# Power1.net
KiCad netlist of a schematic drawn in Altium Designer
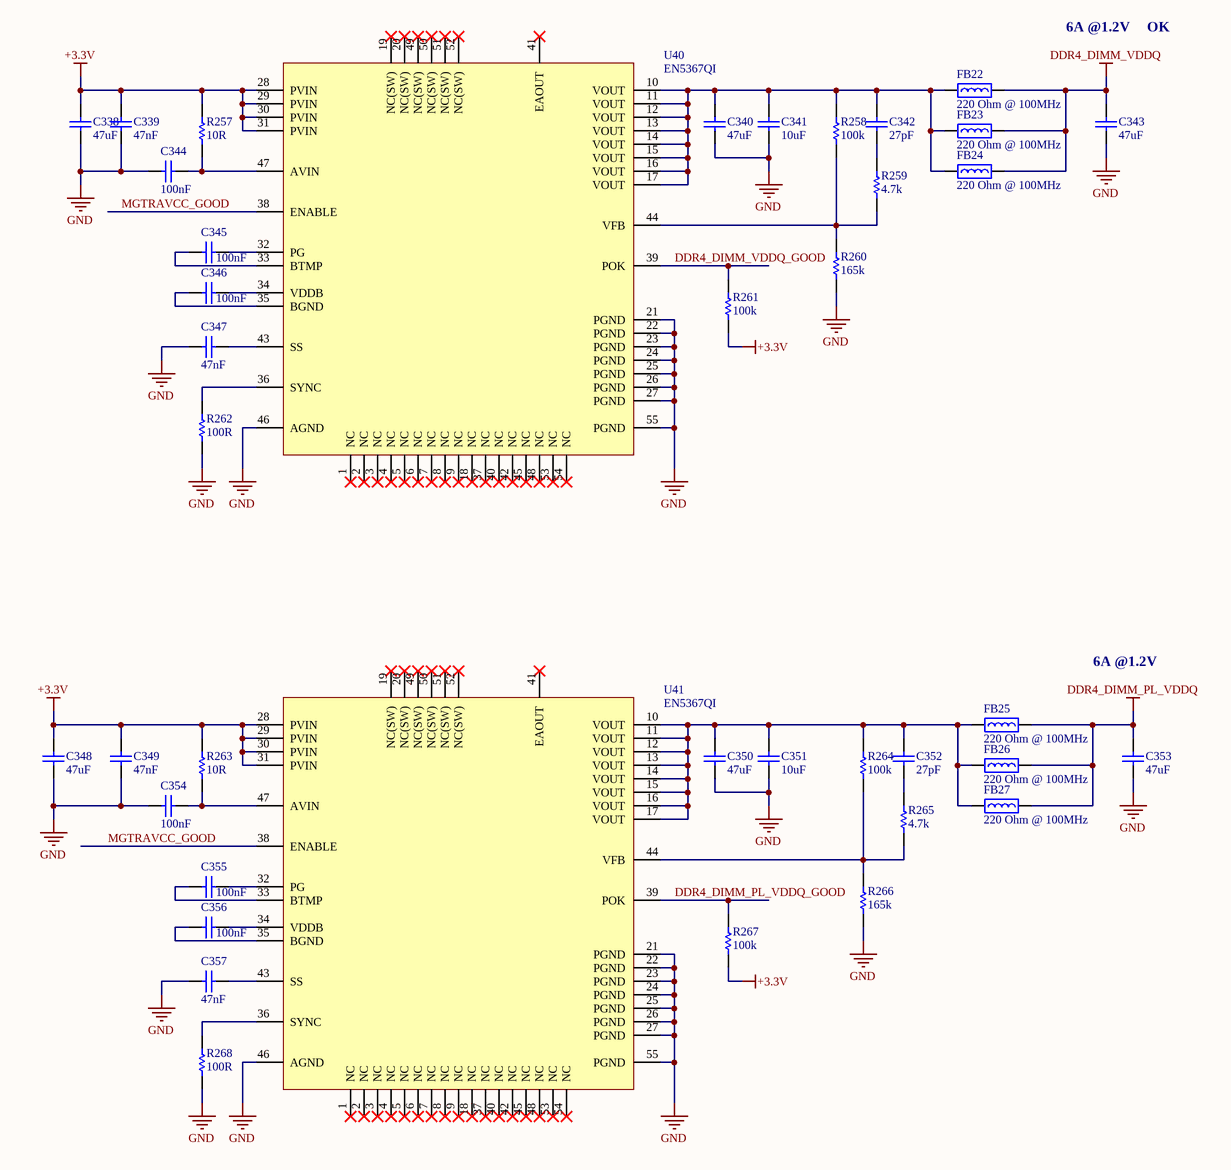
[diagram p0: Power1.SchDoc]

(export (version "E")
  (design (tool "Eeschema 10.0.6"))
  (components
    (comp (ref "C338")
      (value "47uF")
      (footprint "CAPC3216L_1206")
      (description "CAP CER 47UF 25V X5R 1206")
      (fields (field (name "VOLTAGE") "25V") (field (name "TOLERANCE") "20%"))
      (libsource (lib "Ultrascale_SchLib") (part "CAPCER1206X5R47U25V_20T"))
    )
    (comp (ref "C339")
      (value "47nF")
      (footprint "CAPC2012L_0805")
      (description "CAP CER 0.047UF 50V X7R 0805")
      (fields (field (name "VOLTAGE") "50V") (field (name "TOLERANCE") "10%"))
      (libsource (lib "Ultrascale_SchLib") (part "CAPCER0805X5R47N50V_10T"))
    )
    (comp (ref "C340")
      (value "47uF")
      (footprint "CAPC3216L_1206")
      (description "CAP CER 47UF 25V X5R 1206")
      (fields (field (name "VOLTAGE") "25V") (field (name "TOLERANCE") "20%"))
      (libsource (lib "Ultrascale_SchLib") (part "CAPCER1206X5R47U25V_20T"))
    )
    (comp (ref "C341")
      (value "10uF")
      (footprint "CAPC1005L_0402")
      (description "CAP CER 10UF 10V X5R 0402")
      (fields (field (name "VOLTAGE") "10V") (field (name "TOLERANCE") "20%"))
      (libsource (lib "Ultrascale_SchLib") (part "CAPCER0402X5R10U10V_20T"))
    )
    (comp (ref "C342")
      (value "27pF")
      (footprint "CAPC1005L_0402")
      (description "CAP CER 27PF 50V C0G/NP0 0402")
      (fields (field (name "VOLTAGE") "50V") (field (name "TOLERANCE") "5%"))
      (libsource (lib "Ultrascale_SchLib") (part "CAPCER0402C0G27P50V_5T"))
    )
    (comp (ref "C343")
      (value "47uF")
      (footprint "CAPC3216L_1206")
      (description "CAP CER 47UF 25V X5R 1206")
      (fields (field (name "VOLTAGE") "25V") (field (name "TOLERANCE") "20%"))
      (libsource (lib "Ultrascale_SchLib") (part "CAPCER1206X5R47U25V_20T"))
    )
    (comp (ref "C344")
      (value "100nF")
      (footprint "CAPC1005L_0402")
      (description "CAP CER 0.1UF 25V X7R 0402")
      (fields (field (name "VOLTAGE") "25V") (field (name "TOLERANCE") "10%"))
      (libsource (lib "Ultrascale_SchLib") (part "CAPCER0402X7R100N25V_10T"))
    )
    (comp (ref "C345")
      (value "100nF")
      (footprint "CAPC1005L_0402")
      (description "CAP CER 0.1UF 25V X7R 0402")
      (fields (field (name "VOLTAGE") "25V") (field (name "TOLERANCE") "10%"))
      (libsource (lib "Ultrascale_SchLib") (part "CAPCER0402X7R100N25V_10T"))
    )
    (comp (ref "C346")
      (value "100nF")
      (footprint "CAPC1005L_0402")
      (description "CAP CER 0.1UF 25V X7R 0402")
      (fields (field (name "VOLTAGE") "25V") (field (name "TOLERANCE") "10%"))
      (libsource (lib "Ultrascale_SchLib") (part "CAPCER0402X7R100N25V_10T"))
    )
    (comp (ref "C347")
      (value "47nF")
      (footprint "CAPC2012L_0805")
      (description "CAP CER 0.047UF 50V X7R 0805")
      (fields (field (name "VOLTAGE") "50V") (field (name "TOLERANCE") "10%"))
      (libsource (lib "Ultrascale_SchLib") (part "CAPCER0805X5R47N50V_10T"))
    )
    (comp (ref "C348")
      (value "47uF")
      (footprint "CAPC3216L_1206")
      (description "CAP CER 47UF 25V X5R 1206")
      (fields (field (name "VOLTAGE") "25V") (field (name "TOLERANCE") "20%"))
      (libsource (lib "Ultrascale_SchLib") (part "CAPCER1206X5R47U25V_20T"))
    )
    (comp (ref "C349")
      (value "47nF")
      (footprint "CAPC2012L_0805")
      (description "CAP CER 0.047UF 50V X7R 0805")
      (fields (field (name "VOLTAGE") "50V") (field (name "TOLERANCE") "10%"))
      (libsource (lib "Ultrascale_SchLib") (part "CAPCER0805X5R47N50V_10T"))
    )
    (comp (ref "C350")
      (value "47uF")
      (footprint "CAPC3216L_1206")
      (description "CAP CER 47UF 25V X5R 1206")
      (fields (field (name "VOLTAGE") "25V") (field (name "TOLERANCE") "20%"))
      (libsource (lib "Ultrascale_SchLib") (part "CAPCER1206X5R47U25V_20T"))
    )
    (comp (ref "C351")
      (value "10uF")
      (footprint "CAPC1005L_0402")
      (description "CAP CER 10UF 10V X5R 0402")
      (fields (field (name "VOLTAGE") "10V") (field (name "TOLERANCE") "20%"))
      (libsource (lib "Ultrascale_SchLib") (part "CAPCER0402X5R10U10V_20T"))
    )
    (comp (ref "C352")
      (value "27pF")
      (footprint "CAPC1005L_0402")
      (description "CAP CER 27PF 50V C0G/NP0 0402")
      (fields (field (name "VOLTAGE") "50V") (field (name "TOLERANCE") "5%"))
      (libsource (lib "Ultrascale_SchLib") (part "CAPCER0402C0G27P50V_5T"))
    )
    (comp (ref "C353")
      (value "47uF")
      (footprint "CAPC3216L_1206")
      (description "CAP CER 47UF 25V X5R 1206")
      (fields (field (name "VOLTAGE") "25V") (field (name "TOLERANCE") "20%"))
      (libsource (lib "Ultrascale_SchLib") (part "CAPCER1206X5R47U25V_20T"))
    )
    (comp (ref "C354")
      (value "100nF")
      (footprint "CAPC1005L_0402")
      (description "CAP CER 0.1UF 25V X7R 0402")
      (fields (field (name "VOLTAGE") "25V") (field (name "TOLERANCE") "10%"))
      (libsource (lib "Ultrascale_SchLib") (part "CAPCER0402X7R100N25V_10T"))
    )
    (comp (ref "C355")
      (value "100nF")
      (footprint "CAPC1005L_0402")
      (description "CAP CER 0.1UF 25V X7R 0402")
      (fields (field (name "VOLTAGE") "25V") (field (name "TOLERANCE") "10%"))
      (libsource (lib "Ultrascale_SchLib") (part "CAPCER0402X7R100N25V_10T"))
    )
    (comp (ref "C356")
      (value "100nF")
      (footprint "CAPC1005L_0402")
      (description "CAP CER 0.1UF 25V X7R 0402")
      (fields (field (name "VOLTAGE") "25V") (field (name "TOLERANCE") "10%"))
      (libsource (lib "Ultrascale_SchLib") (part "CAPCER0402X7R100N25V_10T"))
    )
    (comp (ref "C357")
      (value "47nF")
      (footprint "CAPC2012L_0805")
      (description "CAP CER 0.047UF 50V X7R 0805")
      (fields (field (name "VOLTAGE") "50V") (field (name "TOLERANCE") "10%"))
      (libsource (lib "Ultrascale_SchLib") (part "CAPCER0805X5R47N50V_10T"))
    )
    (comp (ref "FB22")
      (value "BEAD0603_220_2A5_40M")
      (footprint "INDC1608N_0603")
      (description "FERRITE BEAD 220 OHM 0603 1LN")
      (fields (field (name "IMPEDANCE @ FREQUENCY") "220 Ohm @ 100MHz"))
      (libsource (lib "Ultrascale_SchLib") (part "BEAD0603_220_2A5_40M"))
    )
    (comp (ref "FB23")
      (value "BEAD0603_220_2A5_40M")
      (footprint "INDC1608N_0603")
      (description "FERRITE BEAD 220 OHM 0603 1LN")
      (fields (field (name "IMPEDANCE @ FREQUENCY") "220 Ohm @ 100MHz"))
      (libsource (lib "Ultrascale_SchLib") (part "BEAD0603_220_2A5_40M"))
    )
    (comp (ref "FB24")
      (value "BEAD0603_220_2A5_40M")
      (footprint "INDC1608N_0603")
      (description "FERRITE BEAD 220 OHM 0603 1LN")
      (fields (field (name "IMPEDANCE @ FREQUENCY") "220 Ohm @ 100MHz"))
      (libsource (lib "Ultrascale_SchLib") (part "BEAD0603_220_2A5_40M"))
    )
    (comp (ref "FB25")
      (value "BEAD0603_220_2A5_40M")
      (footprint "INDC1608N_0603")
      (description "FERRITE BEAD 220 OHM 0603 1LN")
      (fields (field (name "IMPEDANCE @ FREQUENCY") "220 Ohm @ 100MHz"))
      (libsource (lib "Ultrascale_SchLib") (part "BEAD0603_220_2A5_40M"))
    )
    (comp (ref "FB26")
      (value "BEAD0603_220_2A5_40M")
      (footprint "INDC1608N_0603")
      (description "FERRITE BEAD 220 OHM 0603 1LN")
      (fields (field (name "IMPEDANCE @ FREQUENCY") "220 Ohm @ 100MHz"))
      (libsource (lib "Ultrascale_SchLib") (part "BEAD0603_220_2A5_40M"))
    )
    (comp (ref "FB27")
      (value "BEAD0603_220_2A5_40M")
      (footprint "INDC1608N_0603")
      (description "FERRITE BEAD 220 OHM 0603 1LN")
      (fields (field (name "IMPEDANCE @ FREQUENCY") "220 Ohm @ 100MHz"))
      (libsource (lib "Ultrascale_SchLib") (part "BEAD0603_220_2A5_40M"))
    )
    (comp (ref "R257")
      (value "10R")
      (footprint "RESC1005L_0402")
      (description "RES SMD 10 OHM 1% 1/10W 0402")
      (fields (field (name "POWER") "1/10W") (field (name "TOLERANCE") "1%"))
      (libsource (lib "Ultrascale_SchLib") (part "RES0402_10R_0W1_1T"))
    )
    (comp (ref "R258")
      (value "100k")
      (footprint "RESC1005L_0402")
      (description "RES SMD 100K OHM 1% 1/5W 0402")
      (fields (field (name "POWER") "1/5W") (field (name "TOLERANCE") "1%"))
      (libsource (lib "Ultrascale_SchLib") (part "RES0402_100K_0W2_1T"))
    )
    (comp (ref "R259")
      (value "4.7k")
      (footprint "RESC1005L_0402")
      (description "RES SMD 4.7K OHM 1% 1/10W 0402")
      (fields (field (name "POWER") "1/10W") (field (name "TOLERANCE") "1%"))
      (libsource (lib "Ultrascale_SchLib") (part "RES0402_4K7_0W1_1T"))
    )
    (comp (ref "R260")
      (value "165k")
      (footprint "RESC1005L_0402")
      (description "RES SMD 165K OHM 1% 1/10W 0402")
      (fields (field (name "POWER") "1/10W") (field (name "TOLERANCE") "±1%"))
      (libsource (lib "Ultrascale_SchLib") (part "RES0402_165K_0W1_1T"))
    )
    (comp (ref "R261")
      (value "100k")
      (footprint "RESC1005L_0402")
      (description "RES SMD 100K OHM 1% 1/5W 0402")
      (fields (field (name "POWER") "1/5W") (field (name "TOLERANCE") "1%"))
      (libsource (lib "Ultrascale_SchLib") (part "RES0402_100K_0W2_1T"))
    )
    (comp (ref "R262")
      (value "100R")
      (footprint "RESC1005L_0402")
      (description "RES SMD 100 OHM 1% 1/10W 0402")
      (fields (field (name "POWER") "1/10W") (field (name "TOLERANCE") "1%"))
      (libsource (lib "Ultrascale_SchLib") (part "RES0402_100R_0W1_1T"))
    )
    (comp (ref "R263")
      (value "10R")
      (footprint "RESC1005L_0402")
      (description "RES SMD 10 OHM 1% 1/10W 0402")
      (fields (field (name "POWER") "1/10W") (field (name "TOLERANCE") "1%"))
      (libsource (lib "Ultrascale_SchLib") (part "RES0402_10R_0W1_1T"))
    )
    (comp (ref "R264")
      (value "100k")
      (footprint "RESC1005L_0402")
      (description "RES SMD 100K OHM 1% 1/5W 0402")
      (fields (field (name "POWER") "1/5W") (field (name "TOLERANCE") "1%"))
      (libsource (lib "Ultrascale_SchLib") (part "RES0402_100K_0W2_1T"))
    )
    (comp (ref "R265")
      (value "4.7k")
      (footprint "RESC1005L_0402")
      (description "RES SMD 4.7K OHM 1% 1/10W 0402")
      (fields (field (name "POWER") "1/10W") (field (name "TOLERANCE") "1%"))
      (libsource (lib "Ultrascale_SchLib") (part "RES0402_4K7_0W1_1T"))
    )
    (comp (ref "R266")
      (value "165k")
      (footprint "RESC1005L_0402")
      (description "RES SMD 165K OHM 1% 1/10W 0402")
      (fields (field (name "POWER") "1/10W") (field (name "TOLERANCE") "±1%"))
      (libsource (lib "Ultrascale_SchLib") (part "RES0402_165K_0W1_1T"))
    )
    (comp (ref "R267")
      (value "100k")
      (footprint "RESC1005L_0402")
      (description "RES SMD 100K OHM 1% 1/5W 0402")
      (fields (field (name "POWER") "1/5W") (field (name "TOLERANCE") "1%"))
      (libsource (lib "Ultrascale_SchLib") (part "RES0402_100K_0W2_1T"))
    )
    (comp (ref "R268")
      (value "100R")
      (footprint "RESC1005L_0402")
      (description "RES SMD 100 OHM 1% 1/10W 0402")
      (fields (field (name "POWER") "1/10W") (field (name "TOLERANCE") "1%"))
      (libsource (lib "Ultrascale_SchLib") (part "RES0402_100R_0W1_1T"))
    )
    (comp (ref "U40")
      (value "EN5367QI")
      (footprint "QFN54-EN5367QI")
      (description "DC/DC CONVERTER 0.6-4.9V 29W")
      (libsource (lib "Ultrascale_SchLib") (part "EN5367QI"))
    )
    (comp (ref "U41")
      (value "EN5367QI")
      (footprint "QFN54-EN5367QI")
      (description "DC/DC CONVERTER 0.6-4.9V 29W")
      (libsource (lib "Ultrascale_SchLib") (part "EN5367QI"))
    )
  )
  (nets
    (net (code "1") (name "+3.3V") (class "Default")
      (node (ref "C338") (pin "2") (pinfunction "2_2") (pintype "passive"))
      (node (ref "C339") (pin "2") (pinfunction "2_2") (pintype "passive"))
      (node (ref "C348") (pin "2") (pinfunction "2_2") (pintype "passive"))
      (node (ref "C349") (pin "2") (pinfunction "2_2") (pintype "passive"))
      (node (ref "R257") (pin "2") (pinfunction "2_2") (pintype "passive"))
      (node (ref "R261") (pin "2") (pinfunction "2_2") (pintype "passive"))
      (node (ref "R263") (pin "2") (pinfunction "2_2") (pintype "passive"))
      (node (ref "R267") (pin "2") (pinfunction "2_2") (pintype "passive"))
      (node (ref "U40") (pin "28") (pinfunction "PVIN_28") (pintype "power_in"))
      (node (ref "U40") (pin "29") (pinfunction "PVIN_29") (pintype "power_in"))
      (node (ref "U40") (pin "30") (pinfunction "PVIN_30") (pintype "power_in"))
      (node (ref "U40") (pin "31") (pinfunction "PVIN_31") (pintype "power_in"))
      (node (ref "U41") (pin "28") (pinfunction "PVIN_28") (pintype "power_in"))
      (node (ref "U41") (pin "29") (pinfunction "PVIN_29") (pintype "power_in"))
      (node (ref "U41") (pin "30") (pinfunction "PVIN_30") (pintype "power_in"))
      (node (ref "U41") (pin "31") (pinfunction "PVIN_31") (pintype "power_in"))
    )
    (net (code "2") (name "/DDR4_DIMM_PL_VDDQ_GOOD") (class "Default")
      (node (ref "R267") (pin "1") (pinfunction "1_1") (pintype "passive"))
      (node (ref "U41") (pin "39") (pinfunction "POK_39") (pintype "power_in"))
    )
    (net (code "3") (name "/DDR4_DIMM_VDDQ_GOOD") (class "Default")
      (node (ref "R261") (pin "1") (pinfunction "1_1") (pintype "passive"))
      (node (ref "U40") (pin "39") (pinfunction "POK_39") (pintype "power_in"))
    )
    (net (code "4") (name "/MGTRAVCC_GOOD") (class "Default")
      (node (ref "U40") (pin "38") (pinfunction "ENABLE_38") (pintype "power_in"))
      (node (ref "U41") (pin "38") (pinfunction "ENABLE_38") (pintype "power_in"))
    )
    (net (code "5") (name "DDR4_DIMM_PL_VDDQ") (class "Default")
      (node (ref "C353") (pin "2") (pinfunction "2_2") (pintype "passive"))
      (node (ref "FB25") (pin "2") (pinfunction "2_2") (pintype "passive"))
      (node (ref "FB26") (pin "2") (pinfunction "2_2") (pintype "passive"))
      (node (ref "FB27") (pin "2") (pinfunction "2_2") (pintype "passive"))
    )
    (net (code "6") (name "DDR4_DIMM_VDDQ") (class "Default")
      (node (ref "C343") (pin "2") (pinfunction "2_2") (pintype "passive"))
      (node (ref "FB22") (pin "2") (pinfunction "2_2") (pintype "passive"))
      (node (ref "FB23") (pin "2") (pinfunction "2_2") (pintype "passive"))
      (node (ref "FB24") (pin "2") (pinfunction "2_2") (pintype "passive"))
    )
    (net (code "7") (name "GND") (class "Default")
      (node (ref "C338") (pin "1") (pinfunction "1_1") (pintype "passive"))
      (node (ref "C339") (pin "1") (pinfunction "1_1") (pintype "passive"))
      (node (ref "C340") (pin "1") (pinfunction "1_1") (pintype "passive"))
      (node (ref "C341") (pin "1") (pinfunction "1_1") (pintype "passive"))
      (node (ref "C343") (pin "1") (pinfunction "1_1") (pintype "passive"))
      (node (ref "C344") (pin "2") (pinfunction "2_2") (pintype "passive"))
      (node (ref "C347") (pin "2") (pinfunction "2_2") (pintype "passive"))
      (node (ref "C348") (pin "1") (pinfunction "1_1") (pintype "passive"))
      (node (ref "C349") (pin "1") (pinfunction "1_1") (pintype "passive"))
      (node (ref "C350") (pin "1") (pinfunction "1_1") (pintype "passive"))
      (node (ref "C351") (pin "1") (pinfunction "1_1") (pintype "passive"))
      (node (ref "C353") (pin "1") (pinfunction "1_1") (pintype "passive"))
      (node (ref "C354") (pin "2") (pinfunction "2_2") (pintype "passive"))
      (node (ref "C357") (pin "2") (pinfunction "2_2") (pintype "passive"))
      (node (ref "R260") (pin "1") (pinfunction "1_1") (pintype "passive"))
      (node (ref "R262") (pin "2") (pinfunction "2_2") (pintype "passive"))
      (node (ref "R266") (pin "1") (pinfunction "1_1") (pintype "passive"))
      (node (ref "R268") (pin "2") (pinfunction "2_2") (pintype "passive"))
      (node (ref "U40") (pin "21") (pinfunction "PGND_21") (pintype "power_in"))
      (node (ref "U40") (pin "22") (pinfunction "PGND_22") (pintype "power_in"))
      (node (ref "U40") (pin "23") (pinfunction "PGND_23") (pintype "power_in"))
      (node (ref "U40") (pin "24") (pinfunction "PGND_24") (pintype "power_in"))
      (node (ref "U40") (pin "25") (pinfunction "PGND_25") (pintype "power_in"))
      (node (ref "U40") (pin "26") (pinfunction "PGND_26") (pintype "power_in"))
      (node (ref "U40") (pin "27") (pinfunction "PGND_27") (pintype "power_in"))
      (node (ref "U40") (pin "46") (pinfunction "AGND_46") (pintype "power_in"))
      (node (ref "U40") (pin "55") (pinfunction "PGND_55") (pintype "power_in"))
      (node (ref "U41") (pin "21") (pinfunction "PGND_21") (pintype "power_in"))
      (node (ref "U41") (pin "22") (pinfunction "PGND_22") (pintype "power_in"))
      (node (ref "U41") (pin "23") (pinfunction "PGND_23") (pintype "power_in"))
      (node (ref "U41") (pin "24") (pinfunction "PGND_24") (pintype "power_in"))
      (node (ref "U41") (pin "25") (pinfunction "PGND_25") (pintype "power_in"))
      (node (ref "U41") (pin "26") (pinfunction "PGND_26") (pintype "power_in"))
      (node (ref "U41") (pin "27") (pinfunction "PGND_27") (pintype "power_in"))
      (node (ref "U41") (pin "46") (pinfunction "AGND_46") (pintype "power_in"))
      (node (ref "U41") (pin "55") (pinfunction "PGND_55") (pintype "power_in"))
    )
    (net (code "8") (name "Net-(C340-Pad2)") (class "Default")
      (node (ref "C340") (pin "2") (pinfunction "2_2") (pintype "passive"))
      (node (ref "C341") (pin "2") (pinfunction "2_2") (pintype "passive"))
      (node (ref "C342") (pin "2") (pinfunction "2_2") (pintype "passive"))
      (node (ref "FB22") (pin "1") (pinfunction "1_1") (pintype "passive"))
      (node (ref "FB23") (pin "1") (pinfunction "1_1") (pintype "passive"))
      (node (ref "FB24") (pin "1") (pinfunction "1_1") (pintype "passive"))
      (node (ref "R258") (pin "2") (pinfunction "2_2") (pintype "passive"))
      (node (ref "U40") (pin "10") (pinfunction "VOUT_10") (pintype "power_in"))
      (node (ref "U40") (pin "11") (pinfunction "VOUT_11") (pintype "power_in"))
      (node (ref "U40") (pin "12") (pinfunction "VOUT_12") (pintype "power_in"))
      (node (ref "U40") (pin "13") (pinfunction "VOUT_13") (pintype "power_in"))
      (node (ref "U40") (pin "14") (pinfunction "VOUT_14") (pintype "power_in"))
      (node (ref "U40") (pin "15") (pinfunction "VOUT_15") (pintype "power_in"))
      (node (ref "U40") (pin "16") (pinfunction "VOUT_16") (pintype "power_in"))
      (node (ref "U40") (pin "17") (pinfunction "VOUT_17") (pintype "power_in"))
    )
    (net (code "9") (name "Net-(C342-Pad1)") (class "Default")
      (node (ref "C342") (pin "1") (pinfunction "1_1") (pintype "passive"))
      (node (ref "R259") (pin "2") (pinfunction "2_2") (pintype "passive"))
    )
    (net (code "10") (name "Net-(C350-Pad2)") (class "Default")
      (node (ref "C350") (pin "2") (pinfunction "2_2") (pintype "passive"))
      (node (ref "C351") (pin "2") (pinfunction "2_2") (pintype "passive"))
      (node (ref "C352") (pin "2") (pinfunction "2_2") (pintype "passive"))
      (node (ref "FB25") (pin "1") (pinfunction "1_1") (pintype "passive"))
      (node (ref "FB26") (pin "1") (pinfunction "1_1") (pintype "passive"))
      (node (ref "FB27") (pin "1") (pinfunction "1_1") (pintype "passive"))
      (node (ref "R264") (pin "2") (pinfunction "2_2") (pintype "passive"))
      (node (ref "U41") (pin "10") (pinfunction "VOUT_10") (pintype "power_in"))
      (node (ref "U41") (pin "11") (pinfunction "VOUT_11") (pintype "power_in"))
      (node (ref "U41") (pin "12") (pinfunction "VOUT_12") (pintype "power_in"))
      (node (ref "U41") (pin "13") (pinfunction "VOUT_13") (pintype "power_in"))
      (node (ref "U41") (pin "14") (pinfunction "VOUT_14") (pintype "power_in"))
      (node (ref "U41") (pin "15") (pinfunction "VOUT_15") (pintype "power_in"))
      (node (ref "U41") (pin "16") (pinfunction "VOUT_16") (pintype "power_in"))
      (node (ref "U41") (pin "17") (pinfunction "VOUT_17") (pintype "power_in"))
    )
    (net (code "11") (name "Net-(C352-Pad1)") (class "Default")
      (node (ref "C352") (pin "1") (pinfunction "1_1") (pintype "passive"))
      (node (ref "R265") (pin "2") (pinfunction "2_2") (pintype "passive"))
    )
    (net (code "12") (name "Net-(U40-AVIN)") (class "Default")
      (node (ref "C344") (pin "1") (pinfunction "1_1") (pintype "passive"))
      (node (ref "R257") (pin "1") (pinfunction "1_1") (pintype "passive"))
      (node (ref "U40") (pin "47") (pinfunction "AVIN_47") (pintype "power_in"))
    )
    (net (code "13") (name "Net-(U40-BGND)") (class "Default")
      (node (ref "C346") (pin "2") (pinfunction "2_2") (pintype "passive"))
      (node (ref "U40") (pin "35") (pinfunction "BGND_35") (pintype "power_in"))
    )
    (net (code "14") (name "Net-(U40-BTMP)") (class "Default")
      (node (ref "C345") (pin "2") (pinfunction "2_2") (pintype "passive"))
      (node (ref "U40") (pin "33") (pinfunction "BTMP_33") (pintype "power_in"))
    )
    (net (code "15") (name "Net-(U40-PG)") (class "Default")
      (node (ref "C345") (pin "1") (pinfunction "1_1") (pintype "passive"))
      (node (ref "U40") (pin "32") (pinfunction "PG_32") (pintype "power_in"))
    )
    (net (code "16") (name "Net-(U40-SS)") (class "Default")
      (node (ref "C347") (pin "1") (pinfunction "1_1") (pintype "passive"))
      (node (ref "U40") (pin "43") (pinfunction "SS_43") (pintype "power_in"))
    )
    (net (code "17") (name "Net-(U40-SYNC)") (class "Default")
      (node (ref "R262") (pin "1") (pinfunction "1_1") (pintype "passive"))
      (node (ref "U40") (pin "36") (pinfunction "SYNC_36") (pintype "power_in"))
    )
    (net (code "18") (name "Net-(U40-VDDB)") (class "Default")
      (node (ref "C346") (pin "1") (pinfunction "1_1") (pintype "passive"))
      (node (ref "U40") (pin "34") (pinfunction "VDDB_34") (pintype "power_in"))
    )
    (net (code "19") (name "Net-(U40-VFB)") (class "Default")
      (node (ref "R258") (pin "1") (pinfunction "1_1") (pintype "passive"))
      (node (ref "R259") (pin "1") (pinfunction "1_1") (pintype "passive"))
      (node (ref "R260") (pin "2") (pinfunction "2_2") (pintype "passive"))
      (node (ref "U40") (pin "44") (pinfunction "VFB_44") (pintype "power_in"))
    )
    (net (code "20") (name "Net-(U41-AVIN)") (class "Default")
      (node (ref "C354") (pin "1") (pinfunction "1_1") (pintype "passive"))
      (node (ref "R263") (pin "1") (pinfunction "1_1") (pintype "passive"))
      (node (ref "U41") (pin "47") (pinfunction "AVIN_47") (pintype "power_in"))
    )
    (net (code "21") (name "Net-(U41-BGND)") (class "Default")
      (node (ref "C356") (pin "2") (pinfunction "2_2") (pintype "passive"))
      (node (ref "U41") (pin "35") (pinfunction "BGND_35") (pintype "power_in"))
    )
    (net (code "22") (name "Net-(U41-BTMP)") (class "Default")
      (node (ref "C355") (pin "2") (pinfunction "2_2") (pintype "passive"))
      (node (ref "U41") (pin "33") (pinfunction "BTMP_33") (pintype "power_in"))
    )
    (net (code "23") (name "Net-(U41-PG)") (class "Default")
      (node (ref "C355") (pin "1") (pinfunction "1_1") (pintype "passive"))
      (node (ref "U41") (pin "32") (pinfunction "PG_32") (pintype "power_in"))
    )
    (net (code "24") (name "Net-(U41-SS)") (class "Default")
      (node (ref "C357") (pin "1") (pinfunction "1_1") (pintype "passive"))
      (node (ref "U41") (pin "43") (pinfunction "SS_43") (pintype "power_in"))
    )
    (net (code "25") (name "Net-(U41-SYNC)") (class "Default")
      (node (ref "R268") (pin "1") (pinfunction "1_1") (pintype "passive"))
      (node (ref "U41") (pin "36") (pinfunction "SYNC_36") (pintype "power_in"))
    )
    (net (code "26") (name "Net-(U41-VDDB)") (class "Default")
      (node (ref "C356") (pin "1") (pinfunction "1_1") (pintype "passive"))
      (node (ref "U41") (pin "34") (pinfunction "VDDB_34") (pintype "power_in"))
    )
    (net (code "27") (name "Net-(U41-VFB)") (class "Default")
      (node (ref "R264") (pin "1") (pinfunction "1_1") (pintype "passive"))
      (node (ref "R265") (pin "1") (pinfunction "1_1") (pintype "passive"))
      (node (ref "R266") (pin "2") (pinfunction "2_2") (pintype "passive"))
      (node (ref "U41") (pin "44") (pinfunction "VFB_44") (pintype "power_in"))
    )
    (net (code "28") (name "unconnected-(U40-EAOUT-Pad41)") (class "Default")
      (node (ref "U40") (pin "41") (pinfunction "EAOUT_41") (pintype "power_in+no_connect"))
    )
    (net (code "29") (name "unconnected-(U40-NC(SW)-Pad19)") (class "Default")
      (node (ref "U40") (pin "19") (pinfunction "NC(SW)_19") (pintype "power_in+no_connect"))
    )
    (net (code "30") (name "unconnected-(U40-NC(SW)-Pad20)") (class "Default")
      (node (ref "U40") (pin "20") (pinfunction "NC(SW)_20") (pintype "power_in+no_connect"))
    )
    (net (code "31") (name "unconnected-(U40-NC(SW)-Pad49)") (class "Default")
      (node (ref "U40") (pin "49") (pinfunction "NC(SW)_49") (pintype "power_in+no_connect"))
    )
    (net (code "32") (name "unconnected-(U40-NC(SW)-Pad50)") (class "Default")
      (node (ref "U40") (pin "50") (pinfunction "NC(SW)_50") (pintype "power_in+no_connect"))
    )
    (net (code "33") (name "unconnected-(U40-NC(SW)-Pad51)") (class "Default")
      (node (ref "U40") (pin "51") (pinfunction "NC(SW)_51") (pintype "power_in+no_connect"))
    )
    (net (code "34") (name "unconnected-(U40-NC(SW)-Pad52)") (class "Default")
      (node (ref "U40") (pin "52") (pinfunction "NC(SW)_52") (pintype "power_in+no_connect"))
    )
    (net (code "35") (name "unconnected-(U40-NC-Pad1)") (class "Default")
      (node (ref "U40") (pin "1") (pinfunction "NC_1") (pintype "power_in+no_connect"))
    )
    (net (code "36") (name "unconnected-(U40-NC-Pad2)") (class "Default")
      (node (ref "U40") (pin "2") (pinfunction "NC_2") (pintype "power_in+no_connect"))
    )
    (net (code "37") (name "unconnected-(U40-NC-Pad3)") (class "Default")
      (node (ref "U40") (pin "3") (pinfunction "NC_3") (pintype "power_in+no_connect"))
    )
    (net (code "38") (name "unconnected-(U40-NC-Pad4)") (class "Default")
      (node (ref "U40") (pin "4") (pinfunction "NC_4") (pintype "power_in+no_connect"))
    )
    (net (code "39") (name "unconnected-(U40-NC-Pad5)") (class "Default")
      (node (ref "U40") (pin "5") (pinfunction "NC_5") (pintype "power_in+no_connect"))
    )
    (net (code "40") (name "unconnected-(U40-NC-Pad6)") (class "Default")
      (node (ref "U40") (pin "6") (pinfunction "NC_6") (pintype "power_in+no_connect"))
    )
    (net (code "41") (name "unconnected-(U40-NC-Pad7)") (class "Default")
      (node (ref "U40") (pin "7") (pinfunction "NC_7") (pintype "power_in+no_connect"))
    )
    (net (code "42") (name "unconnected-(U40-NC-Pad8)") (class "Default")
      (node (ref "U40") (pin "8") (pinfunction "NC_8") (pintype "power_in+no_connect"))
    )
    (net (code "43") (name "unconnected-(U40-NC-Pad9)") (class "Default")
      (node (ref "U40") (pin "9") (pinfunction "NC_9") (pintype "power_in+no_connect"))
    )
    (net (code "44") (name "unconnected-(U40-NC-Pad18)") (class "Default")
      (node (ref "U40") (pin "18") (pinfunction "NC_18") (pintype "power_in+no_connect"))
    )
    (net (code "45") (name "unconnected-(U40-NC-Pad37)") (class "Default")
      (node (ref "U40") (pin "37") (pinfunction "NC_37") (pintype "power_in+no_connect"))
    )
    (net (code "46") (name "unconnected-(U40-NC-Pad40)") (class "Default")
      (node (ref "U40") (pin "40") (pinfunction "NC_40") (pintype "power_in+no_connect"))
    )
    (net (code "47") (name "unconnected-(U40-NC-Pad42)") (class "Default")
      (node (ref "U40") (pin "42") (pinfunction "NC_42") (pintype "power_in+no_connect"))
    )
    (net (code "48") (name "unconnected-(U40-NC-Pad45)") (class "Default")
      (node (ref "U40") (pin "45") (pinfunction "NC_45") (pintype "power_in+no_connect"))
    )
    (net (code "49") (name "unconnected-(U40-NC-Pad48)") (class "Default")
      (node (ref "U40") (pin "48") (pinfunction "NC_48") (pintype "power_in+no_connect"))
    )
    (net (code "50") (name "unconnected-(U40-NC-Pad53)") (class "Default")
      (node (ref "U40") (pin "53") (pinfunction "NC_53") (pintype "power_in+no_connect"))
    )
    (net (code "51") (name "unconnected-(U40-NC-Pad54)") (class "Default")
      (node (ref "U40") (pin "54") (pinfunction "NC_54") (pintype "power_in+no_connect"))
    )
    (net (code "52") (name "unconnected-(U41-EAOUT-Pad41)") (class "Default")
      (node (ref "U41") (pin "41") (pinfunction "EAOUT_41") (pintype "power_in+no_connect"))
    )
    (net (code "53") (name "unconnected-(U41-NC(SW)-Pad19)") (class "Default")
      (node (ref "U41") (pin "19") (pinfunction "NC(SW)_19") (pintype "power_in+no_connect"))
    )
    (net (code "54") (name "unconnected-(U41-NC(SW)-Pad20)") (class "Default")
      (node (ref "U41") (pin "20") (pinfunction "NC(SW)_20") (pintype "power_in+no_connect"))
    )
    (net (code "55") (name "unconnected-(U41-NC(SW)-Pad49)") (class "Default")
      (node (ref "U41") (pin "49") (pinfunction "NC(SW)_49") (pintype "power_in+no_connect"))
    )
    (net (code "56") (name "unconnected-(U41-NC(SW)-Pad50)") (class "Default")
      (node (ref "U41") (pin "50") (pinfunction "NC(SW)_50") (pintype "power_in+no_connect"))
    )
    (net (code "57") (name "unconnected-(U41-NC(SW)-Pad51)") (class "Default")
      (node (ref "U41") (pin "51") (pinfunction "NC(SW)_51") (pintype "power_in+no_connect"))
    )
    (net (code "58") (name "unconnected-(U41-NC(SW)-Pad52)") (class "Default")
      (node (ref "U41") (pin "52") (pinfunction "NC(SW)_52") (pintype "power_in+no_connect"))
    )
    (net (code "59") (name "unconnected-(U41-NC-Pad1)") (class "Default")
      (node (ref "U41") (pin "1") (pinfunction "NC_1") (pintype "power_in+no_connect"))
    )
    (net (code "60") (name "unconnected-(U41-NC-Pad2)") (class "Default")
      (node (ref "U41") (pin "2") (pinfunction "NC_2") (pintype "power_in+no_connect"))
    )
    (net (code "61") (name "unconnected-(U41-NC-Pad3)") (class "Default")
      (node (ref "U41") (pin "3") (pinfunction "NC_3") (pintype "power_in+no_connect"))
    )
    (net (code "62") (name "unconnected-(U41-NC-Pad4)") (class "Default")
      (node (ref "U41") (pin "4") (pinfunction "NC_4") (pintype "power_in+no_connect"))
    )
    (net (code "63") (name "unconnected-(U41-NC-Pad5)") (class "Default")
      (node (ref "U41") (pin "5") (pinfunction "NC_5") (pintype "power_in+no_connect"))
    )
    (net (code "64") (name "unconnected-(U41-NC-Pad6)") (class "Default")
      (node (ref "U41") (pin "6") (pinfunction "NC_6") (pintype "power_in+no_connect"))
    )
    (net (code "65") (name "unconnected-(U41-NC-Pad7)") (class "Default")
      (node (ref "U41") (pin "7") (pinfunction "NC_7") (pintype "power_in+no_connect"))
    )
    (net (code "66") (name "unconnected-(U41-NC-Pad8)") (class "Default")
      (node (ref "U41") (pin "8") (pinfunction "NC_8") (pintype "power_in+no_connect"))
    )
    (net (code "67") (name "unconnected-(U41-NC-Pad9)") (class "Default")
      (node (ref "U41") (pin "9") (pinfunction "NC_9") (pintype "power_in+no_connect"))
    )
    (net (code "68") (name "unconnected-(U41-NC-Pad18)") (class "Default")
      (node (ref "U41") (pin "18") (pinfunction "NC_18") (pintype "power_in+no_connect"))
    )
    (net (code "69") (name "unconnected-(U41-NC-Pad37)") (class "Default")
      (node (ref "U41") (pin "37") (pinfunction "NC_37") (pintype "power_in+no_connect"))
    )
    (net (code "70") (name "unconnected-(U41-NC-Pad40)") (class "Default")
      (node (ref "U41") (pin "40") (pinfunction "NC_40") (pintype "power_in+no_connect"))
    )
    (net (code "71") (name "unconnected-(U41-NC-Pad42)") (class "Default")
      (node (ref "U41") (pin "42") (pinfunction "NC_42") (pintype "power_in+no_connect"))
    )
    (net (code "72") (name "unconnected-(U41-NC-Pad45)") (class "Default")
      (node (ref "U41") (pin "45") (pinfunction "NC_45") (pintype "power_in+no_connect"))
    )
    (net (code "73") (name "unconnected-(U41-NC-Pad48)") (class "Default")
      (node (ref "U41") (pin "48") (pinfunction "NC_48") (pintype "power_in+no_connect"))
    )
    (net (code "74") (name "unconnected-(U41-NC-Pad53)") (class "Default")
      (node (ref "U41") (pin "53") (pinfunction "NC_53") (pintype "power_in+no_connect"))
    )
    (net (code "75") (name "unconnected-(U41-NC-Pad54)") (class "Default")
      (node (ref "U41") (pin "54") (pinfunction "NC_54") (pintype "power_in+no_connect"))
    )
  )
)
